# Connectors.net
KiCad netlist of a schematic drawn in Altium Designer
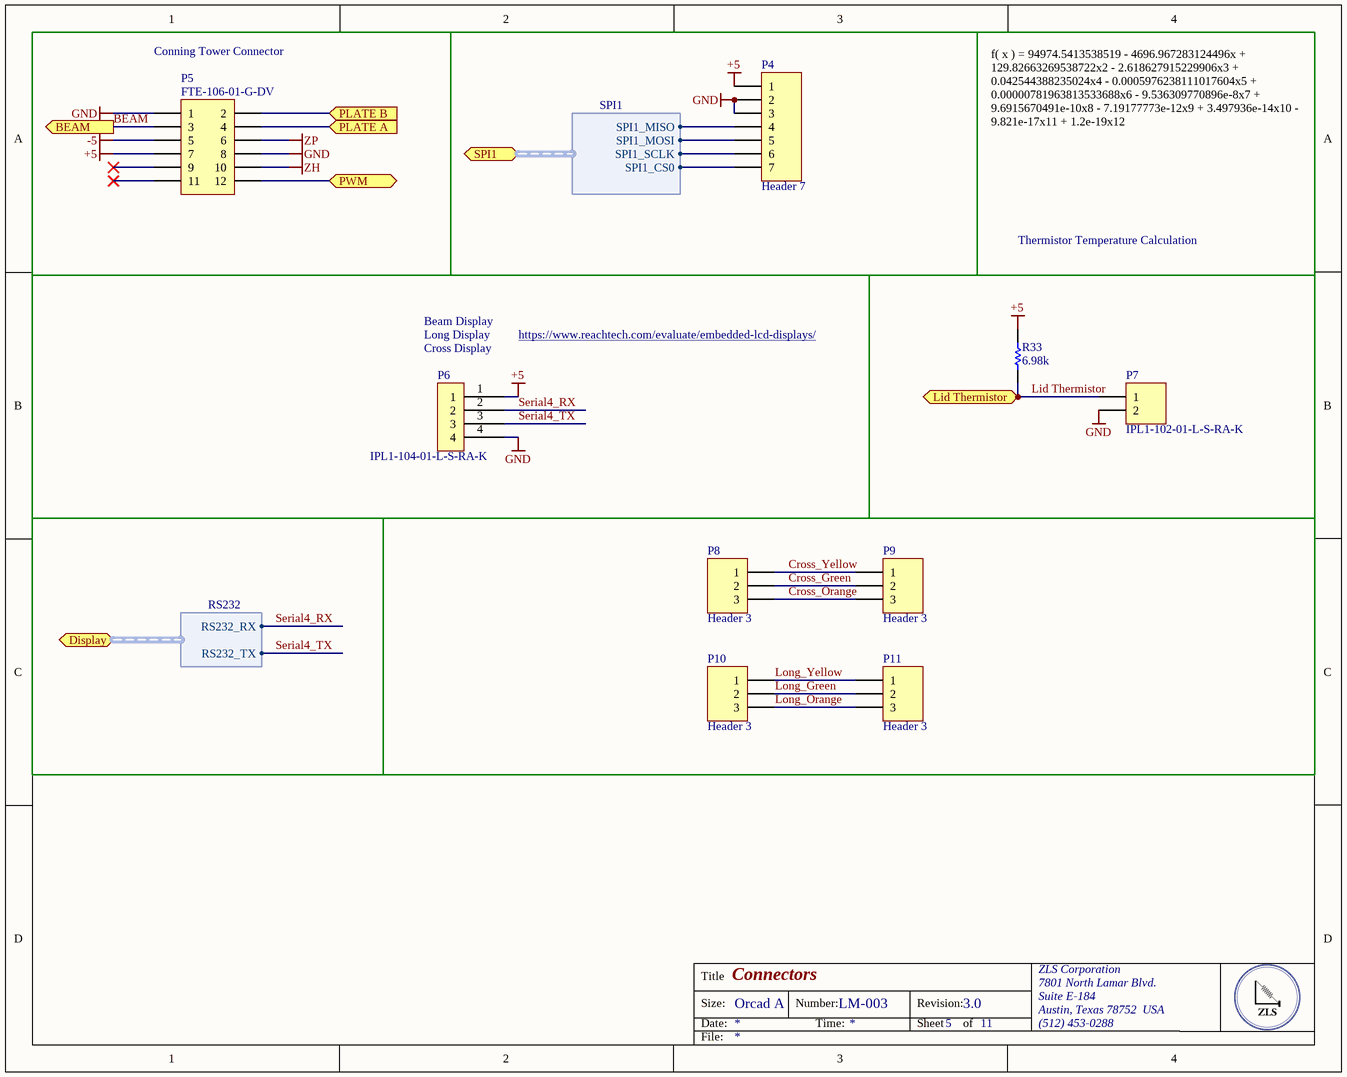
[diagram p0: Connectors.SchDoc]

(export (version "E")
  (design (tool "Eeschema 10.0.6"))
  (components
    (comp (ref "P4")
      (value "Header 7")
      (footprint "HDR1X7")
      (description "Header, 7-Pin")
      (fields (field (name "PUBLISHER") "Altium Limited"))
      (libsource (lib "Miscellaneous Connectors") (part "Header 7"))
    )
    (comp (ref "P5")
      (value "FTE-106-01-G-DV")
      (footprint "FTSH-106-01")
      (description "Header, 6-Pin, Dual row")
      (fields (field (name "MANUFACTURER") "Samtec") (field (name "PUBLISHER") "Altium Limited"))
      (libsource (lib "Conning Tower Adapter") (part "Header 6X2"))
    )
    (comp (ref "P6")
      (value "IPL1-104-01-L-S-RA-K")
      (footprint "IPL1-104-01")
      (description ".100 TERMINAL ASSY")
      (libsource (lib "ZLS_LIB") (part "53047-0410"))
    )
    (comp (ref "P7")
      (value "IPL1-102-01-L-S-RA-K")
      (footprint "IPL1-102-01")
      (description "CONN SHROUDED PWR HEADER 2POS")
      (libsource (lib "Miscellaneous Connectors") (part "Header 2H"))
    )
    (comp (ref "P8")
      (value "Header 3")
      (footprint "HDR1X3")
      (description "Header, 3-Pin")
      (fields (field (name "PUBLISHER") "Altium Limited"))
      (libsource (lib "Miscellaneous Connectors") (part "Header 3"))
    )
    (comp (ref "P9")
      (value "Header 3")
      (footprint "HDR1X3")
      (description "Header, 3-Pin")
      (fields (field (name "PUBLISHER") "Altium Limited"))
      (libsource (lib "") (part "Header 3_1"))
    )
    (comp (ref "P10")
      (value "Header 3")
      (footprint "HDR1X3")
      (description "Header, 3-Pin")
      (fields (field (name "PUBLISHER") "Altium Limited"))
      (libsource (lib "Miscellaneous Connectors") (part "Header 3"))
    )
    (comp (ref "P11")
      (value "Header 3")
      (footprint "HDR1X3")
      (description "Header, 3-Pin")
      (fields (field (name "PUBLISHER") "Altium Limited"))
      (libsource (lib "") (part "Header 3_1"))
    )
    (comp (ref "R33")
      (value "6K98 1% 0805(2012)")
      (footprint "RESC0805(2012)_N")
      (description "6K98 0.125W 1% 0805 (2012 Metric)  SMD")
      (fields
        (field (name "MANUFACTURER") "Vishay Dale")
        (field (name "MANUFACTURER PART NUMBER") "CRCW08056K98FKEA")
        (field (name "RESISTANCE (OHMS)") "6.98k")
      )
      (libsource (lib "Altium Content Vault") (part "CMP-1013-00606-1"))
    )
  )
  (nets
    (net (code "3") (name "+5") (class "Default")
      (node (ref "P4") (pin "1") (pinfunction "1_1") (pintype "passive"))
      (node (ref "P5") (pin "7") (pinfunction "7_7") (pintype "passive"))
      (node (ref "P6") (pin "1") (pinfunction "1_1") (pintype "passive"))
      (node (ref "R33") (pin "2") (pinfunction "2_2") (pintype "passive"))
    )
    (net (code "4") (name "-5") (class "Default")
      (node (ref "P5") (pin "5") (pinfunction "5_5") (pintype "passive"))
    )
    (net (code "5") (name "/BEAM") (class "Default")
      (node (ref "P5") (pin "3") (pinfunction "3_3") (pintype "passive"))
    )
    (net (code "6") (name "/Cross_Green") (class "Default")
      (node (ref "P8") (pin "2") (pinfunction "2_2") (pintype "passive"))
      (node (ref "P9") (pin "2") (pinfunction "2_2") (pintype "passive"))
    )
    (net (code "7") (name "/Cross_Orange") (class "Default")
      (node (ref "P8") (pin "3") (pinfunction "3_3") (pintype "passive"))
      (node (ref "P9") (pin "3") (pinfunction "3_3") (pintype "passive"))
    )
    (net (code "8") (name "/Cross_Yellow") (class "Default")
      (node (ref "P8") (pin "1") (pinfunction "1_1") (pintype "passive"))
      (node (ref "P9") (pin "1") (pinfunction "1_1") (pintype "passive"))
    )
    (net (code "9") (name "/Lid Thermistor") (class "Default")
      (node (ref "P7") (pin "1") (pinfunction "1_1") (pintype "passive"))
      (node (ref "R33") (pin "1") (pinfunction "1_1") (pintype "passive"))
    )
    (net (code "10") (name "/Long_Green") (class "Default")
      (node (ref "P10") (pin "2") (pinfunction "2_2") (pintype "passive"))
      (node (ref "P11") (pin "2") (pinfunction "2_2") (pintype "passive"))
    )
    (net (code "11") (name "/Long_Orange") (class "Default")
      (node (ref "P10") (pin "3") (pinfunction "3_3") (pintype "passive"))
      (node (ref "P11") (pin "3") (pinfunction "3_3") (pintype "passive"))
    )
    (net (code "12") (name "/Long_Yellow") (class "Default")
      (node (ref "P10") (pin "1") (pinfunction "1_1") (pintype "passive"))
      (node (ref "P11") (pin "1") (pinfunction "1_1") (pintype "passive"))
    )
    (net (code "13") (name "/PLATE A") (class "Default")
      (node (ref "P5") (pin "4") (pinfunction "4_4") (pintype "passive"))
    )
    (net (code "14") (name "/PLATE B") (class "Default")
      (node (ref "P5") (pin "2") (pinfunction "2_2") (pintype "passive"))
    )
    (net (code "15") (name "/PWM") (class "Default")
      (node (ref "P5") (pin "12") (pinfunction "12_12") (pintype "passive"))
    )
    (net (code "16") (name "/SPI1_CS0") (class "Default")
      (node (ref "P4") (pin "7") (pinfunction "7_7") (pintype "passive"))
    )
    (net (code "17") (name "/SPI1_MISO") (class "Default")
      (node (ref "P4") (pin "4") (pinfunction "4_4") (pintype "passive"))
    )
    (net (code "18") (name "/SPI1_MOSI") (class "Default")
      (node (ref "P4") (pin "5") (pinfunction "5_5") (pintype "passive"))
    )
    (net (code "19") (name "/SPI1_SCLK") (class "Default")
      (node (ref "P4") (pin "6") (pinfunction "6_6") (pintype "passive"))
    )
    (net (code "20") (name "/Serial4_RX") (class "Default")
      (node (ref "P6") (pin "2") (pinfunction "2_2") (pintype "passive"))
    )
    (net (code "21") (name "/Serial4_TX") (class "Default")
      (node (ref "P6") (pin "3") (pinfunction "3_3") (pintype "passive"))
    )
    (net (code "24") (name "GND") (class "Default")
      (node (ref "P4") (pin "2") (pinfunction "2_2") (pintype "passive"))
      (node (ref "P4") (pin "3") (pinfunction "3_3") (pintype "passive"))
      (node (ref "P5") (pin "1") (pinfunction "1_1") (pintype "passive"))
      (node (ref "P5") (pin "8") (pinfunction "8_8") (pintype "passive"))
      (node (ref "P6") (pin "4") (pinfunction "4_4") (pintype "passive"))
      (node (ref "P7") (pin "2") (pinfunction "2_2") (pintype "passive"))
    )
    (net (code "25") (name "ZH") (class "Default")
      (node (ref "P5") (pin "10") (pinfunction "10_10") (pintype "passive"))
    )
    (net (code "26") (name "ZP") (class "Default")
      (node (ref "P5") (pin "6") (pinfunction "6_6") (pintype "passive"))
    )
    (net (code "27") (name "unconnected-(P5-Pad9)") (class "Default")
      (node (ref "P5") (pin "9") (pinfunction "9_9") (pintype "passive+no_connect"))
    )
    (net (code "28") (name "unconnected-(P5-Pad11)") (class "Default")
      (node (ref "P5") (pin "11") (pinfunction "11_11") (pintype "passive+no_connect"))
    )
  )
)
